# wifi_main.net
KiCad netlist of a schematic drawn in EAGLE
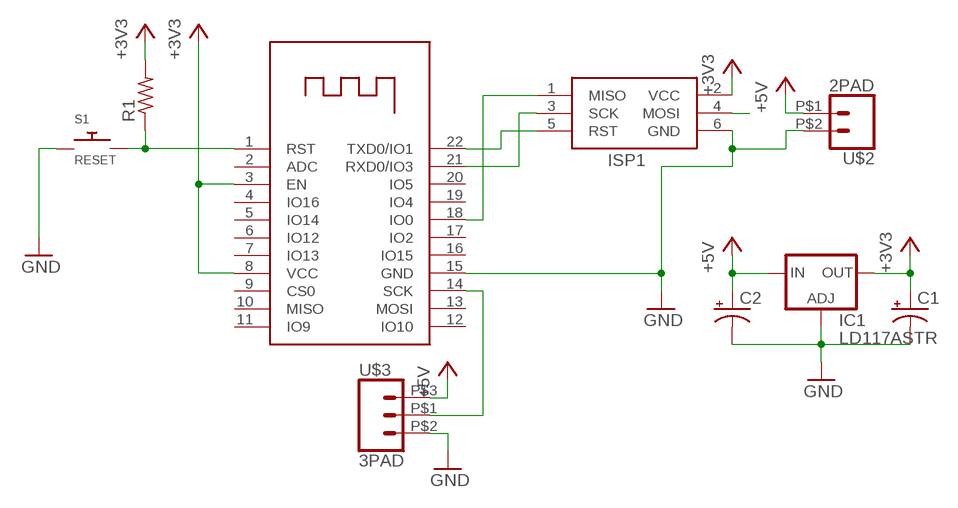
[diagram p0: schematic, sheet 1]

(export (version "E")
  (design (tool "Eeschema 10.0.6"))
  (components
    (comp (ref "C1")
      (value "CPOL-US153CLV-0405")
      (footprint "eagle-import:153CLV-0405")
      (libsource (lib "eagle-import") (part "CPOL-US153CLV-0405"))
    )
    (comp (ref "C2")
      (value "CPOL-US153CLV-0405")
      (footprint "eagle-import:153CLV-0405")
      (libsource (lib "eagle-import") (part "CPOL-US153CLV-0405"))
    )
    (comp (ref "IC1")
      (value "LD117ASTR")
      (footprint "eagle-import:SOT223")
      (libsource (lib "eagle-import") (part "LD117A?STR"))
    )
    (comp (ref "ISP1")
      (value "AVRISP-6")
      (footprint "eagle-import:AVRISP")
      (libsource (lib "eagle-import") (part "AVRISP-6"))
    )
    (comp (ref "R1")
      (value "R-US_R0805")
      (footprint "eagle-import:R0805")
      (libsource (lib "eagle-import") (part "R-US_R0805"))
    )
    (comp (ref "S1")
      (value "RESET")
      (footprint "eagle-import:B3F-1000")
      (libsource (lib "eagle-import") (part "BUTTON"))
    )
    (comp (ref "U$1")
      (value "ESP-12F")
      (footprint "eagle-import:ESP-12F")
      (libsource (lib "eagle-import") (part "ESP-12F"))
    )
    (comp (ref "U$2")
      (value "2PAD")
      (footprint "eagle-import:2PAD")
      (libsource (lib "eagle-import") (part "2PAD"))
    )
    (comp (ref "U$3")
      (value "3PAD")
      (footprint "eagle-import:3PAD")
      (libsource (lib "eagle-import") (part "3PAD"))
    )
  )
  (nets
    (net (code "1") (name "+3V3") (class "Default")
      (node (ref "C1") (pin "+") (pinfunction "+_+") (pintype "passive"))
      (node (ref "IC1") (pin "4") (pinfunction "OUT_4") (pintype "passive"))
      (node (ref "ISP1") (pin "2") (pinfunction "VCC_2") (pintype "power_in"))
      (node (ref "R1") (pin "2") (pinfunction "2_2") (pintype "passive"))
      (node (ref "U$1") (pin "3") (pinfunction "EN_3") (pintype "bidirectional"))
      (node (ref "U$1") (pin "8") (pinfunction "VCC_8") (pintype "bidirectional"))
    )
    (net (code "2") (name "+5V") (class "Default")
      (node (ref "C2") (pin "+") (pinfunction "+_+") (pintype "passive"))
      (node (ref "IC1") (pin "3") (pinfunction "IN_3") (pintype "input"))
      (node (ref "U$2") (pin "P$1") (pinfunction "1_P$1") (pintype "passive"))
      (node (ref "U$3") (pin "P$3") (pinfunction "3_P$3") (pintype "passive"))
    )
    (net (code "3") (name "GND") (class "Default")
      (node (ref "C1") (pin "-") (pinfunction "-_-") (pintype "passive"))
      (node (ref "C2") (pin "-") (pinfunction "-_-") (pintype "passive"))
      (node (ref "IC1") (pin "1") (pinfunction "ADJ_1") (pintype "input"))
      (node (ref "ISP1") (pin "6") (pinfunction "GND_6") (pintype "power_in"))
      (node (ref "S1") (pin "1") (pinfunction "P$1_1") (pintype "passive"))
      (node (ref "S1") (pin "2") (pinfunction "P$1_2") (pintype "passive"))
      (node (ref "U$1") (pin "15") (pinfunction "GND_15") (pintype "bidirectional"))
      (node (ref "U$2") (pin "P$2") (pinfunction "2_P$2") (pintype "passive"))
      (node (ref "U$3") (pin "P$2") (pinfunction "1_P$2") (pintype "passive"))
    )
    (net (code "4") (name "Net-(ISP1-MISO)") (class "Default")
      (node (ref "ISP1") (pin "1") (pinfunction "MISO_1") (pintype "input"))
      (node (ref "U$1") (pin "18") (pinfunction "IO0_18") (pintype "bidirectional"))
    )
    (net (code "5") (name "Net-(ISP1-RST)") (class "Default")
      (node (ref "ISP1") (pin "5") (pinfunction "RST_5") (pintype "output"))
      (node (ref "U$1") (pin "22") (pinfunction "TXD0/IO1_22") (pintype "bidirectional"))
    )
    (net (code "6") (name "Net-(ISP1-SCK)") (class "Default")
      (node (ref "ISP1") (pin "3") (pinfunction "SCK_3") (pintype "output"))
      (node (ref "U$1") (pin "21") (pinfunction "RXD0/IO3_21") (pintype "bidirectional"))
    )
    (net (code "7") (name "Net-(U$1-RST)") (class "Default")
      (node (ref "R1") (pin "1") (pinfunction "1_1") (pintype "passive"))
      (node (ref "S1") (pin "3") (pinfunction "P$2_3") (pintype "passive"))
      (node (ref "S1") (pin "4") (pinfunction "P$2_4") (pintype "passive"))
      (node (ref "U$1") (pin "1") (pinfunction "RST_1") (pintype "bidirectional"))
    )
    (net (code "8") (name "Net-(U$1-SCK)") (class "Default")
      (node (ref "U$1") (pin "14") (pinfunction "SCK_14") (pintype "bidirectional"))
      (node (ref "U$3") (pin "P$1") (pinfunction "2_P$1") (pintype "passive"))
    )
    (net (code "9") (name "unconnected-(ISP1-MOSI-Pad4)") (class "Default")
      (node (ref "ISP1") (pin "4") (pinfunction "MOSI_4") (pintype "output"))
    )
    (net (code "10") (name "unconnected-(U$1-ADC-Pad2)") (class "Default")
      (node (ref "U$1") (pin "2") (pinfunction "ADC_2") (pintype "bidirectional"))
    )
    (net (code "11") (name "unconnected-(U$1-CS0-Pad9)") (class "Default")
      (node (ref "U$1") (pin "9") (pinfunction "CS0_9") (pintype "bidirectional"))
    )
    (net (code "12") (name "unconnected-(U$1-IO2-Pad17)") (class "Default")
      (node (ref "U$1") (pin "17") (pinfunction "IO2_17") (pintype "bidirectional"))
    )
    (net (code "13") (name "unconnected-(U$1-IO4-Pad19)") (class "Default")
      (node (ref "U$1") (pin "19") (pinfunction "IO4_19") (pintype "bidirectional"))
    )
    (net (code "14") (name "unconnected-(U$1-IO5-Pad20)") (class "Default")
      (node (ref "U$1") (pin "20") (pinfunction "IO5_20") (pintype "bidirectional"))
    )
    (net (code "15") (name "unconnected-(U$1-IO9-Pad11)") (class "Default")
      (node (ref "U$1") (pin "11") (pinfunction "IO9_11") (pintype "bidirectional"))
    )
    (net (code "16") (name "unconnected-(U$1-IO10-Pad12)") (class "Default")
      (node (ref "U$1") (pin "12") (pinfunction "IO10_12") (pintype "bidirectional"))
    )
    (net (code "17") (name "unconnected-(U$1-IO12-Pad6)") (class "Default")
      (node (ref "U$1") (pin "6") (pinfunction "IO12_6") (pintype "bidirectional"))
    )
    (net (code "18") (name "unconnected-(U$1-IO13-Pad7)") (class "Default")
      (node (ref "U$1") (pin "7") (pinfunction "IO13_7") (pintype "bidirectional"))
    )
    (net (code "19") (name "unconnected-(U$1-IO14-Pad5)") (class "Default")
      (node (ref "U$1") (pin "5") (pinfunction "IO14_5") (pintype "bidirectional"))
    )
    (net (code "20") (name "unconnected-(U$1-IO15-Pad16)") (class "Default")
      (node (ref "U$1") (pin "16") (pinfunction "IO15_16") (pintype "bidirectional"))
    )
    (net (code "21") (name "unconnected-(U$1-IO16-Pad4)") (class "Default")
      (node (ref "U$1") (pin "4") (pinfunction "IO16_4") (pintype "bidirectional"))
    )
    (net (code "22") (name "unconnected-(U$1-MISO-Pad10)") (class "Default")
      (node (ref "U$1") (pin "10") (pinfunction "MISO_10") (pintype "bidirectional"))
    )
    (net (code "23") (name "unconnected-(U$1-MOSI-Pad13)") (class "Default")
      (node (ref "U$1") (pin "13") (pinfunction "MOSI_13") (pintype "bidirectional"))
    )
  )
)
